# PecanFemto3.net
KiCad netlist of a schematic drawn in EAGLE
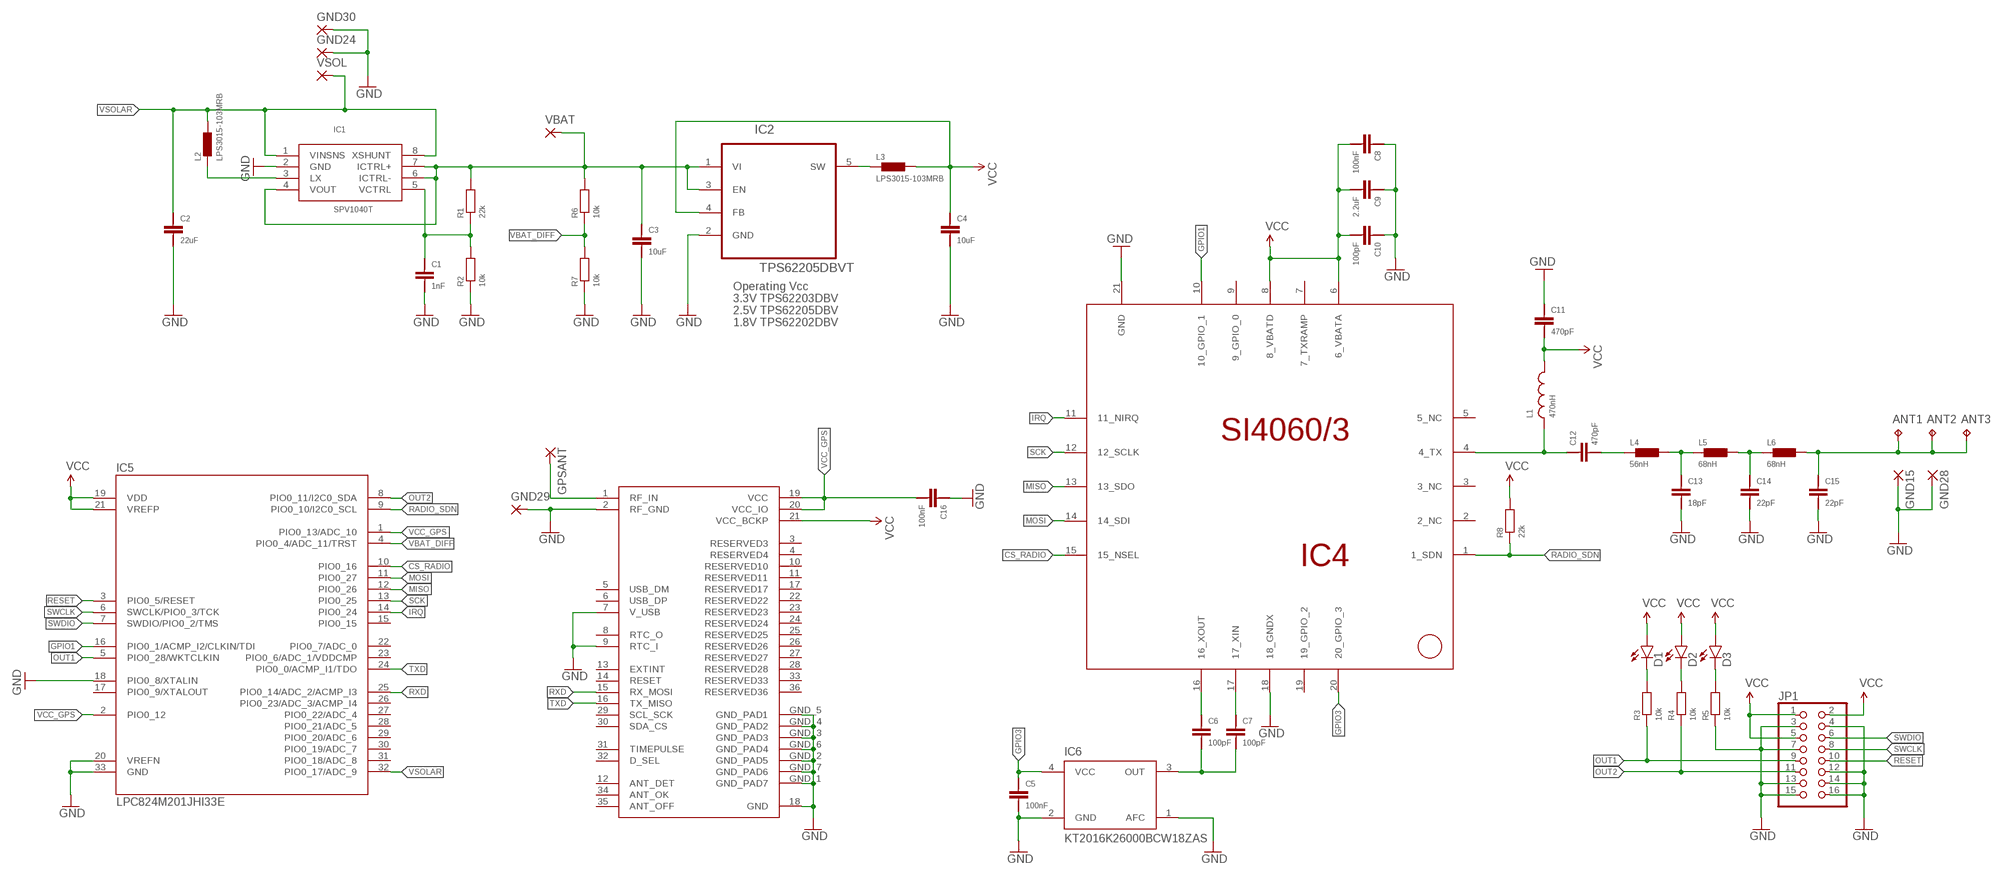
[diagram p0: schematic, sheet 1]

(export (version "E")
  (design (tool "Eeschema 10.0.6"))
  (components
    (comp (ref "ANT1")
      (value "TP")
      (footprint "eagle-import:P1-7")
      (fields (field (name "MPN") "ERJ-3EKF62R0V"))
      (libsource (lib "eagle-import") (part "TP"))
    )
    (comp (ref "ANT2")
      (value "TP")
      (footprint "eagle-import:P1-7")
      (fields (field (name "MPN") "ERJ-3EKF62R0V"))
      (libsource (lib "eagle-import") (part "TP"))
    )
    (comp (ref "ANT3")
      (value "TP")
      (footprint "eagle-import:P1-7")
      (fields (field (name "MPN") "ERJ-3EKF62R0V"))
      (libsource (lib "eagle-import") (part "TP"))
    )
    (comp (ref "C1")
      (value "1nF")
      (footprint "eagle-import:0402")
      (libsource (lib "eagle-import") (part "CAP-0402"))
    )
    (comp (ref "C2")
      (value "22uF")
      (footprint "eagle-import:0805")
      (libsource (lib "eagle-import") (part "CAP-0805"))
    )
    (comp (ref "C3")
      (value "10uF")
      (footprint "eagle-import:0805")
      (libsource (lib "eagle-import") (part "CAP-0805"))
    )
    (comp (ref "C4")
      (value "10uF")
      (footprint "eagle-import:0805")
      (libsource (lib "eagle-import") (part "CAP-0805"))
    )
    (comp (ref "C5")
      (value "100nF")
      (footprint "eagle-import:0402")
      (libsource (lib "eagle-import") (part "CAP-0402"))
    )
    (comp (ref "C6")
      (value "100pF")
      (footprint "eagle-import:0402")
      (libsource (lib "eagle-import") (part "CAP-0402"))
    )
    (comp (ref "C7")
      (value "100pF")
      (footprint "eagle-import:0402")
      (libsource (lib "eagle-import") (part "CAP-0402"))
    )
    (comp (ref "C8")
      (value "100nF")
      (footprint "eagle-import:0402")
      (libsource (lib "eagle-import") (part "CAP-0402"))
    )
    (comp (ref "C9")
      (value "2.2uF")
      (footprint "eagle-import:0402")
      (libsource (lib "eagle-import") (part "CAP-0402"))
    )
    (comp (ref "C10")
      (value "100pF")
      (footprint "eagle-import:0402")
      (libsource (lib "eagle-import") (part "CAP-0402"))
    )
    (comp (ref "C11")
      (value "470pF")
      (footprint "eagle-import:0402")
      (libsource (lib "eagle-import") (part "CAP-0402"))
    )
    (comp (ref "C12")
      (value "470pF")
      (footprint "eagle-import:0402")
      (libsource (lib "eagle-import") (part "CAP-0402"))
    )
    (comp (ref "C13")
      (value "18pF")
      (footprint "eagle-import:0402")
      (libsource (lib "eagle-import") (part "CAP-0402"))
    )
    (comp (ref "C14")
      (value "22pF")
      (footprint "eagle-import:0402")
      (libsource (lib "eagle-import") (part "CAP-0402"))
    )
    (comp (ref "C15")
      (value "22pF")
      (footprint "eagle-import:0402")
      (libsource (lib "eagle-import") (part "CAP-0402"))
    )
    (comp (ref "C16")
      (value "100nF")
      (footprint "eagle-import:0402")
      (libsource (lib "eagle-import") (part "CAP-0402"))
    )
    (comp (ref "D1")
      (value "LED0603")
      (footprint "eagle-import:LED-0603")
      (libsource (lib "eagle-import") (part "LED0603"))
    )
    (comp (ref "D2")
      (value "LED0603")
      (footprint "eagle-import:LED-0603")
      (libsource (lib "eagle-import") (part "LED0603"))
    )
    (comp (ref "D3")
      (value "LED0603")
      (footprint "eagle-import:LED-0603")
      (libsource (lib "eagle-import") (part "LED0603"))
    )
    (comp (ref "GND15")
      (value "SMD2")
      (footprint "eagle-import:SMD1,27-2,54")
      (libsource (lib "eagle-import") (part "SMD2"))
    )
    (comp (ref "GND24")
      (value "SMD2")
      (footprint "eagle-import:SMD1,27-2,54")
      (libsource (lib "eagle-import") (part "SMD2"))
    )
    (comp (ref "GND28")
      (value "SMD2")
      (footprint "eagle-import:SMD1,27-2,54")
      (libsource (lib "eagle-import") (part "SMD2"))
    )
    (comp (ref "GND29")
      (value "SMD2")
      (footprint "eagle-import:SMD1,27-2,54")
      (libsource (lib "eagle-import") (part "SMD2"))
    )
    (comp (ref "GND30")
      (value "SMD2")
      (footprint "eagle-import:SMD1,27-2,54")
      (libsource (lib "eagle-import") (part "SMD2"))
    )
    (comp (ref "GPSANT")
      (value "SMD2")
      (footprint "eagle-import:SMD1,27-2,54")
      (libsource (lib "eagle-import") (part "SMD2"))
    )
    (comp (ref "IC1")
      (value "SPV1040T")
      (footprint "eagle-import:TSSOP8")
      (libsource (lib "eagle-import") (part "SPV1040"))
    )
    (comp (ref "IC2")
      (value "TPS62205DBVT")
      (footprint "eagle-import:SOT95P280X145-5N")
      (fields (field (name "MPN") "TPS62203DBVT") (field (name "MF") "TEXAS INSTRUMENTS"))
      (libsource (lib "eagle-import") (part "TPS62203DBVT"))
    )
    (comp (ref "IC3")
      (value "EVA7M")
      (footprint "eagle-import:EVA7M")
      (libsource (lib "eagle-import") (part "EVA7M"))
    )
    (comp (ref "IC4")
      (value "SI4060/3")
      (footprint "eagle-import:QFN-20")
      (libsource (lib "eagle-import") (part "SI4060/3"))
    )
    (comp (ref "IC5")
      (value "LPC824M201JHI33E")
      (footprint "eagle-import:QFN65P500X500X100-33N")
      (libsource (lib "eagle-import") (part "LPC824M201JHI33E"))
    )
    (comp (ref "IC6")
      (value "KT2016K26000BCW18ZAS")
      (footprint "eagle-import:TCXO_2.0X1.6")
      (libsource (lib "eagle-import") (part "TXC_7Z"))
    )
    (comp (ref "JP1")
      (value "PINHD-2X8")
      (footprint "eagle-import:2X08")
      (libsource (lib "eagle-import") (part "PINHD-2X8"))
    )
    (comp (ref "L1")
      (value "470nH")
      (footprint "eagle-import:0805")
      (libsource (lib "eagle-import") (part "INDUCTOR0805"))
    )
    (comp (ref "L2")
      (value "LPS3015-103MRB")
      (footprint "eagle-import:LPS3015")
      (libsource (lib "eagle-import") (part "IND-LPS3015"))
    )
    (comp (ref "L3")
      (value "LPS3015-103MRB")
      (footprint "eagle-import:LPS3015")
      (libsource (lib "eagle-import") (part "IND-LPS3015"))
    )
    (comp (ref "L4")
      (value "56nH")
      (footprint "eagle-import:0402")
      (libsource (lib "eagle-import") (part "IND-0402"))
    )
    (comp (ref "L5")
      (value "68nH")
      (footprint "eagle-import:0402")
      (libsource (lib "eagle-import") (part "IND-0402"))
    )
    (comp (ref "L6")
      (value "68nH")
      (footprint "eagle-import:0402")
      (libsource (lib "eagle-import") (part "IND-0402"))
    )
    (comp (ref "R1")
      (value "22k")
      (footprint "eagle-import:0402")
      (libsource (lib "eagle-import") (part "RES-0402"))
    )
    (comp (ref "R2")
      (value "10k")
      (footprint "eagle-import:0402")
      (libsource (lib "eagle-import") (part "RES-0402"))
    )
    (comp (ref "R3")
      (value "10k")
      (footprint "eagle-import:0402")
      (libsource (lib "eagle-import") (part "RES-0402"))
    )
    (comp (ref "R4")
      (value "10k")
      (footprint "eagle-import:0402")
      (libsource (lib "eagle-import") (part "RES-0402"))
    )
    (comp (ref "R5")
      (value "10k")
      (footprint "eagle-import:0402")
      (libsource (lib "eagle-import") (part "RES-0402"))
    )
    (comp (ref "R6")
      (value "10k")
      (footprint "eagle-import:0402")
      (libsource (lib "eagle-import") (part "RES-0402"))
    )
    (comp (ref "R7")
      (value "10k")
      (footprint "eagle-import:0402")
      (libsource (lib "eagle-import") (part "RES-0402"))
    )
    (comp (ref "R8")
      (value "22k")
      (footprint "eagle-import:0402")
      (libsource (lib "eagle-import") (part "RES-0402"))
    )
    (comp (ref "VBAT")
      (value "SMD2")
      (footprint "eagle-import:SMD1,27-2,54")
      (libsource (lib "eagle-import") (part "SMD2"))
    )
    (comp (ref "VSOL")
      (value "SMD2")
      (footprint "eagle-import:SMD1,27-2,54")
      (libsource (lib "eagle-import") (part "SMD2"))
    )
  )
  (nets
    (net (code "1") (name "CS_RADIO") (class "Default")
      (node (ref "IC4") (pin "15") (pinfunction "15_NSEL_15") (pintype "bidirectional"))
      (node (ref "IC5") (pin "10") (pinfunction "PIO0_16_10") (pintype "bidirectional"))
    )
    (net (code "2") (name "GND") (class "Default")
      (node (ref "C1") (pin "P$1") (pinfunction "1_P$1") (pintype "passive"))
      (node (ref "C10") (pin "P$2") (pinfunction "2_P$2") (pintype "passive"))
      (node (ref "C11") (pin "P$2") (pinfunction "2_P$2") (pintype "passive"))
      (node (ref "C13") (pin "P$1") (pinfunction "1_P$1") (pintype "passive"))
      (node (ref "C14") (pin "P$1") (pinfunction "1_P$1") (pintype "passive"))
      (node (ref "C15") (pin "P$1") (pinfunction "1_P$1") (pintype "passive"))
      (node (ref "C16") (pin "P$2") (pinfunction "2_P$2") (pintype "passive"))
      (node (ref "C2") (pin "P$1") (pinfunction "1_P$1") (pintype "passive"))
      (node (ref "C3") (pin "P$1") (pinfunction "1_P$1") (pintype "passive"))
      (node (ref "C4") (pin "P$1") (pinfunction "1_P$1") (pintype "passive"))
      (node (ref "C5") (pin "P$1") (pinfunction "1_P$1") (pintype "passive"))
      (node (ref "C8") (pin "P$2") (pinfunction "2_P$2") (pintype "passive"))
      (node (ref "C9") (pin "P$2") (pinfunction "2_P$2") (pintype "passive"))
      (node (ref "GND15") (pin "1") (pinfunction "P_1") (pintype "passive"))
      (node (ref "GND24") (pin "1") (pinfunction "P_1") (pintype "passive"))
      (node (ref "GND28") (pin "1") (pinfunction "P_1") (pintype "passive"))
      (node (ref "GND29") (pin "1") (pinfunction "P_1") (pintype "passive"))
      (node (ref "GND30") (pin "1") (pinfunction "P_1") (pintype "passive"))
      (node (ref "IC1") (pin "2") (pinfunction "GND_2") (pintype "bidirectional"))
      (node (ref "IC2") (pin "2") (pinfunction "GND_2") (pintype "passive"))
      (node (ref "IC3") (pin "18") (pinfunction "GND_18") (pintype "bidirectional"))
      (node (ref "IC3") (pin "2") (pinfunction "RF_GND_2") (pintype "bidirectional"))
      (node (ref "IC3") (pin "7") (pinfunction "V_USB_7") (pintype "bidirectional"))
      (node (ref "IC3") (pin "9") (pinfunction "RTC_I_9") (pintype "bidirectional"))
      (node (ref "IC3") (pin "GND_1") (pinfunction "GND_PAD7_GND_1") (pintype "bidirectional"))
      (node (ref "IC3") (pin "GND_2") (pinfunction "GND_PAD5_GND_2") (pintype "bidirectional"))
      (node (ref "IC3") (pin "GND_3") (pinfunction "GND_PAD3_GND_3") (pintype "bidirectional"))
      (node (ref "IC3") (pin "GND_4") (pinfunction "GND_PAD2_GND_4") (pintype "bidirectional"))
      (node (ref "IC3") (pin "GND_5") (pinfunction "GND_PAD1_GND_5") (pintype "bidirectional"))
      (node (ref "IC3") (pin "GND_6") (pinfunction "GND_PAD4_GND_6") (pintype "bidirectional"))
      (node (ref "IC3") (pin "GND_7") (pinfunction "GND_PAD6_GND_7") (pintype "bidirectional"))
      (node (ref "IC4") (pin "18") (pinfunction "18_GNDX_18") (pintype "bidirectional"))
      (node (ref "IC4") (pin "21") (pinfunction "GND_21") (pintype "bidirectional"))
      (node (ref "IC5") (pin "18") (pinfunction "PIO0_8/XTALIN_18") (pintype "bidirectional"))
      (node (ref "IC5") (pin "20") (pinfunction "VREFN_20") (pintype "bidirectional"))
      (node (ref "IC5") (pin "33") (pinfunction "GND_33") (pintype "bidirectional"))
      (node (ref "IC6") (pin "1") (pinfunction "AFC_1") (pintype "bidirectional"))
      (node (ref "IC6") (pin "2") (pinfunction "GND_2") (pintype "bidirectional"))
      (node (ref "JP1") (pin "12") (pinfunction "12_12") (pintype "passive"))
      (node (ref "JP1") (pin "13") (pinfunction "13_13") (pintype "passive"))
      (node (ref "JP1") (pin "14") (pinfunction "14_14") (pintype "passive"))
      (node (ref "JP1") (pin "15") (pinfunction "15_15") (pintype "passive"))
      (node (ref "JP1") (pin "16") (pinfunction "16_16") (pintype "passive"))
      (node (ref "JP1") (pin "3") (pinfunction "3_3") (pintype "passive"))
      (node (ref "JP1") (pin "4") (pinfunction "4_4") (pintype "passive"))
      (node (ref "JP1") (pin "7") (pinfunction "7_7") (pintype "passive"))
      (node (ref "R2") (pin "P$1") (pinfunction "1_P$1") (pintype "passive"))
      (node (ref "R5") (pin "P$1") (pinfunction "1_P$1") (pintype "passive"))
      (node (ref "R7") (pin "P$1") (pinfunction "1_P$1") (pintype "passive"))
    )
    (net (code "3") (name "GPIO1") (class "Default")
      (node (ref "IC4") (pin "10") (pinfunction "10_GPIO_1_10") (pintype "bidirectional"))
      (node (ref "IC5") (pin "16") (pinfunction "PIO0_1/ACMP_I2/CLKIN/TDI_16") (pintype "bidirectional"))
    )
    (net (code "4") (name "GPIO3") (class "Default")
      (node (ref "C5") (pin "P$2") (pinfunction "2_P$2") (pintype "passive"))
      (node (ref "IC4") (pin "20") (pinfunction "20_GPIO_3_20") (pintype "bidirectional"))
      (node (ref "IC6") (pin "4") (pinfunction "VCC_4") (pintype "bidirectional"))
    )
    (net (code "5") (name "IRQ") (class "Default")
      (node (ref "IC4") (pin "11") (pinfunction "11_NIRQ_11") (pintype "bidirectional"))
      (node (ref "IC5") (pin "14") (pinfunction "PIO0_24_14") (pintype "bidirectional"))
    )
    (net (code "6") (name "MISO") (class "Default")
      (node (ref "IC4") (pin "13") (pinfunction "13_SDO_13") (pintype "bidirectional"))
      (node (ref "IC5") (pin "12") (pinfunction "PIO0_26_12") (pintype "bidirectional"))
    )
    (net (code "7") (name "MOSI") (class "Default")
      (node (ref "IC4") (pin "14") (pinfunction "14_SDI_14") (pintype "bidirectional"))
      (node (ref "IC5") (pin "11") (pinfunction "PIO0_27_11") (pintype "bidirectional"))
    )
    (net (code "8") (name "Net-(C1-2)") (class "Default")
      (node (ref "C1") (pin "P$2") (pinfunction "2_P$2") (pintype "passive"))
      (node (ref "IC1") (pin "5") (pinfunction "VCTRL_5") (pintype "bidirectional"))
      (node (ref "R1") (pin "P$1") (pinfunction "1_P$1") (pintype "passive"))
      (node (ref "R2") (pin "P$2") (pinfunction "2_P$2") (pintype "passive"))
    )
    (net (code "9") (name "Net-(C3-2)") (class "Default")
      (node (ref "C3") (pin "P$2") (pinfunction "2_P$2") (pintype "passive"))
      (node (ref "IC1") (pin "4") (pinfunction "VOUT_4") (pintype "bidirectional"))
      (node (ref "IC1") (pin "6") (pinfunction "ICTRL-_6") (pintype "bidirectional"))
      (node (ref "IC1") (pin "7") (pinfunction "ICTRL+_7") (pintype "bidirectional"))
      (node (ref "IC2") (pin "1") (pinfunction "VI_1") (pintype "power_in"))
      (node (ref "IC2") (pin "3") (pinfunction "EN_3") (pintype "input"))
      (node (ref "R1") (pin "P$2") (pinfunction "2_P$2") (pintype "passive"))
      (node (ref "R6") (pin "P$2") (pinfunction "2_P$2") (pintype "passive"))
      (node (ref "VBAT") (pin "1") (pinfunction "P_1") (pintype "passive"))
    )
    (net (code "10") (name "Net-(C6-1)") (class "Default")
      (node (ref "C6") (pin "P$1") (pinfunction "1_P$1") (pintype "passive"))
      (node (ref "C7") (pin "P$1") (pinfunction "1_P$1") (pintype "passive"))
      (node (ref "IC6") (pin "3") (pinfunction "OUT_3") (pintype "bidirectional"))
    )
    (net (code "11") (name "Net-(C6-2)") (class "Default")
      (node (ref "C6") (pin "P$2") (pinfunction "2_P$2") (pintype "passive"))
      (node (ref "IC4") (pin "16") (pinfunction "16_XOUT_16") (pintype "bidirectional"))
    )
    (net (code "12") (name "Net-(C7-2)") (class "Default")
      (node (ref "C7") (pin "P$2") (pinfunction "2_P$2") (pintype "passive"))
      (node (ref "IC4") (pin "17") (pinfunction "17_XIN_17") (pintype "bidirectional"))
    )
    (net (code "13") (name "Net-(C12-1)") (class "Default")
      (node (ref "C12") (pin "P$1") (pinfunction "1_P$1") (pintype "passive"))
      (node (ref "L4") (pin "P$1") (pinfunction "1_P$1") (pintype "passive"))
    )
    (net (code "14") (name "Net-(C12-2)") (class "Default")
      (node (ref "C12") (pin "P$2") (pinfunction "2_P$2") (pintype "passive"))
      (node (ref "IC4") (pin "4") (pinfunction "4_TX_4") (pintype "bidirectional"))
      (node (ref "L1") (pin "1") (pinfunction "1_1") (pintype "passive"))
    )
    (net (code "15") (name "Net-(C13-2)") (class "Default")
      (node (ref "C13") (pin "P$2") (pinfunction "2_P$2") (pintype "passive"))
      (node (ref "L4") (pin "P$2") (pinfunction "2_P$2") (pintype "passive"))
      (node (ref "L5") (pin "P$1") (pinfunction "1_P$1") (pintype "passive"))
    )
    (net (code "16") (name "Net-(C14-2)") (class "Default")
      (node (ref "C14") (pin "P$2") (pinfunction "2_P$2") (pintype "passive"))
      (node (ref "L5") (pin "P$2") (pinfunction "2_P$2") (pintype "passive"))
      (node (ref "L6") (pin "P$1") (pinfunction "1_P$1") (pintype "passive"))
    )
    (net (code "17") (name "Net-(C15-2)") (class "Default")
      (node (ref "ANT1") (pin "TP") (pinfunction "TP_TP") (pintype "input"))
      (node (ref "ANT2") (pin "TP") (pinfunction "TP_TP") (pintype "input"))
      (node (ref "ANT3") (pin "TP") (pinfunction "TP_TP") (pintype "input"))
      (node (ref "C15") (pin "P$2") (pinfunction "2_P$2") (pintype "passive"))
      (node (ref "L6") (pin "P$2") (pinfunction "2_P$2") (pintype "passive"))
    )
    (net (code "18") (name "Net-(GPSANT-P)") (class "Default")
      (node (ref "GPSANT") (pin "1") (pinfunction "P_1") (pintype "passive"))
      (node (ref "IC3") (pin "1") (pinfunction "RF_IN_1") (pintype "bidirectional"))
    )
    (net (code "19") (name "Net-(IC1-LX)") (class "Default")
      (node (ref "IC1") (pin "3") (pinfunction "LX_3") (pintype "bidirectional"))
      (node (ref "L2") (pin "1_1") (pinfunction "1_1_1") (pintype "passive"))
      (node (ref "L2") (pin "1_2") (pinfunction "1_1_2") (pintype "passive"))
      (node (ref "L2") (pin "1_3") (pinfunction "1_1_3") (pintype "passive"))
      (node (ref "L2") (pin "1_4") (pinfunction "1_1_4") (pintype "passive"))
      (node (ref "L2") (pin "1_5") (pinfunction "1_1_5") (pintype "passive"))
      (node (ref "L2") (pin "1_6") (pinfunction "1_1_6") (pintype "passive"))
      (node (ref "L2") (pin "1_7") (pinfunction "1_1_7") (pintype "passive"))
      (node (ref "L2") (pin "1_8") (pinfunction "1_1_8") (pintype "passive"))
      (node (ref "L2") (pin "1_9") (pinfunction "1_1_9") (pintype "passive"))
    )
    (net (code "20") (name "Net-(IC2-SW)") (class "Default")
      (node (ref "IC2") (pin "5") (pinfunction "SW_5") (pintype "output"))
      (node (ref "L3") (pin "1_1") (pinfunction "1_1_1") (pintype "passive"))
      (node (ref "L3") (pin "1_2") (pinfunction "1_1_2") (pintype "passive"))
      (node (ref "L3") (pin "1_3") (pinfunction "1_1_3") (pintype "passive"))
      (node (ref "L3") (pin "1_4") (pinfunction "1_1_4") (pintype "passive"))
      (node (ref "L3") (pin "1_5") (pinfunction "1_1_5") (pintype "passive"))
      (node (ref "L3") (pin "1_6") (pinfunction "1_1_6") (pintype "passive"))
      (node (ref "L3") (pin "1_7") (pinfunction "1_1_7") (pintype "passive"))
      (node (ref "L3") (pin "1_8") (pinfunction "1_1_8") (pintype "passive"))
      (node (ref "L3") (pin "1_9") (pinfunction "1_1_9") (pintype "passive"))
    )
    (net (code "21") (name "Net-(R3-2)") (class "Default")
      (node (ref "D1") (pin "C") (pinfunction "C_C") (pintype "passive"))
      (node (ref "R3") (pin "P$2") (pinfunction "2_P$2") (pintype "passive"))
    )
    (net (code "22") (name "Net-(R4-2)") (class "Default")
      (node (ref "D2") (pin "C") (pinfunction "C_C") (pintype "passive"))
      (node (ref "R4") (pin "P$2") (pinfunction "2_P$2") (pintype "passive"))
    )
    (net (code "23") (name "Net-(R5-2)") (class "Default")
      (node (ref "D3") (pin "C") (pinfunction "C_C") (pintype "passive"))
      (node (ref "R5") (pin "P$2") (pinfunction "2_P$2") (pintype "passive"))
    )
    (net (code "24") (name "OUT1") (class "Default")
      (node (ref "IC5") (pin "5") (pinfunction "PIO0_28/WKTCLKIN_5") (pintype "bidirectional"))
      (node (ref "JP1") (pin "9") (pinfunction "9_9") (pintype "passive"))
      (node (ref "R3") (pin "P$1") (pinfunction "1_P$1") (pintype "passive"))
    )
    (net (code "25") (name "OUT2") (class "Default")
      (node (ref "IC5") (pin "8") (pinfunction "PIO0_11/I2C0_SDA_8") (pintype "bidirectional"))
      (node (ref "JP1") (pin "11") (pinfunction "11_11") (pintype "passive"))
      (node (ref "R4") (pin "P$1") (pinfunction "1_P$1") (pintype "passive"))
    )
    (net (code "26") (name "RADIO_SDN") (class "Default")
      (node (ref "IC4") (pin "1") (pinfunction "1_SDN_1") (pintype "bidirectional"))
      (node (ref "IC5") (pin "9") (pinfunction "PIO0_10/I2C0_SCL_9") (pintype "bidirectional"))
      (node (ref "R8") (pin "P$1") (pinfunction "1_P$1") (pintype "passive"))
    )
    (net (code "27") (name "RESET") (class "Default")
      (node (ref "IC5") (pin "3") (pinfunction "PIO0_5/RESET_3") (pintype "bidirectional"))
      (node (ref "JP1") (pin "10") (pinfunction "10_10") (pintype "passive"))
    )
    (net (code "28") (name "RXD") (class "Default")
      (node (ref "IC3") (pin "15") (pinfunction "RX_MOSI_15") (pintype "bidirectional"))
      (node (ref "IC5") (pin "25") (pinfunction "PIO0_14/ADC_2/ACMP_I3_25") (pintype "bidirectional"))
    )
    (net (code "29") (name "SCK") (class "Default")
      (node (ref "IC4") (pin "12") (pinfunction "12_SCLK_12") (pintype "bidirectional"))
      (node (ref "IC5") (pin "13") (pinfunction "PIO0_25_13") (pintype "bidirectional"))
    )
    (net (code "30") (name "SWCLK") (class "Default")
      (node (ref "IC5") (pin "6") (pinfunction "SWCLK/PIO0_3/TCK_6") (pintype "bidirectional"))
      (node (ref "JP1") (pin "8") (pinfunction "8_8") (pintype "passive"))
    )
    (net (code "31") (name "SWDIO") (class "Default")
      (node (ref "IC5") (pin "7") (pinfunction "SWDIO/PIO0_2/TMS_7") (pintype "bidirectional"))
      (node (ref "JP1") (pin "6") (pinfunction "6_6") (pintype "passive"))
    )
    (net (code "32") (name "TXD") (class "Default")
      (node (ref "IC3") (pin "16") (pinfunction "TX_MISO_16") (pintype "bidirectional"))
      (node (ref "IC5") (pin "24") (pinfunction "PIO0_0/ACMP_I1/TDO_24") (pintype "bidirectional"))
    )
    (net (code "33") (name "VBAT_DIFF") (class "Default")
      (node (ref "IC5") (pin "4") (pinfunction "PIO0_4/ADC_11/TRST_4") (pintype "bidirectional"))
      (node (ref "R6") (pin "P$1") (pinfunction "1_P$1") (pintype "passive"))
      (node (ref "R7") (pin "P$2") (pinfunction "2_P$2") (pintype "passive"))
    )
    (net (code "34") (name "VCC") (class "Default")
      (node (ref "C10") (pin "P$1") (pinfunction "1_P$1") (pintype "passive"))
      (node (ref "C11") (pin "P$1") (pinfunction "1_P$1") (pintype "passive"))
      (node (ref "C4") (pin "P$2") (pinfunction "2_P$2") (pintype "passive"))
      (node (ref "C8") (pin "P$1") (pinfunction "1_P$1") (pintype "passive"))
      (node (ref "C9") (pin "P$1") (pinfunction "1_P$1") (pintype "passive"))
      (node (ref "D1") (pin "A") (pinfunction "A_A") (pintype "passive"))
      (node (ref "D2") (pin "A") (pinfunction "A_A") (pintype "passive"))
      (node (ref "D3") (pin "A") (pinfunction "A_A") (pintype "passive"))
      (node (ref "IC2") (pin "4") (pinfunction "FB_4") (pintype "input"))
      (node (ref "IC3") (pin "21") (pinfunction "VCC_BCKP_21") (pintype "bidirectional"))
      (node (ref "IC4") (pin "6") (pinfunction "6_VBATA_6") (pintype "bidirectional"))
      (node (ref "IC4") (pin "8") (pinfunction "8_VBATD_8") (pintype "bidirectional"))
      (node (ref "IC5") (pin "19") (pinfunction "VDD_19") (pintype "bidirectional"))
      (node (ref "IC5") (pin "21") (pinfunction "VREFP_21") (pintype "bidirectional"))
      (node (ref "JP1") (pin "1") (pinfunction "1_1") (pintype "passive"))
      (node (ref "JP1") (pin "2") (pinfunction "2_2") (pintype "passive"))
      (node (ref "JP1") (pin "5") (pinfunction "5_5") (pintype "passive"))
      (node (ref "L1") (pin "2") (pinfunction "2_2") (pintype "passive"))
      (node (ref "L3") (pin "2_1") (pinfunction "2_2_1") (pintype "passive"))
      (node (ref "L3") (pin "2_2") (pinfunction "2_2_2") (pintype "passive"))
      (node (ref "L3") (pin "2_3") (pinfunction "2_2_3") (pintype "passive"))
      (node (ref "L3") (pin "2_4") (pinfunction "2_2_4") (pintype "passive"))
      (node (ref "L3") (pin "2_5") (pinfunction "2_2_5") (pintype "passive"))
      (node (ref "L3") (pin "2_6") (pinfunction "2_2_6") (pintype "passive"))
      (node (ref "L3") (pin "2_7") (pinfunction "2_2_7") (pintype "passive"))
      (node (ref "L3") (pin "2_8") (pinfunction "2_2_8") (pintype "passive"))
      (node (ref "L3") (pin "2_9") (pinfunction "2_2_9") (pintype "passive"))
      (node (ref "R8") (pin "P$2") (pinfunction "2_P$2") (pintype "passive"))
    )
    (net (code "35") (name "VCC_GPS") (class "Default")
      (node (ref "C16") (pin "P$1") (pinfunction "1_P$1") (pintype "passive"))
      (node (ref "IC3") (pin "19") (pinfunction "VCC_19") (pintype "bidirectional"))
      (node (ref "IC3") (pin "20") (pinfunction "VCC_IO_20") (pintype "bidirectional"))
      (node (ref "IC5") (pin "1") (pinfunction "PIO0_13/ADC_10_1") (pintype "bidirectional"))
      (node (ref "IC5") (pin "2") (pinfunction "PIO0_12_2") (pintype "bidirectional"))
    )
    (net (code "36") (name "VSOLAR") (class "Default")
      (node (ref "C2") (pin "P$2") (pinfunction "2_P$2") (pintype "passive"))
      (node (ref "IC1") (pin "1") (pinfunction "VINSNS_1") (pintype "bidirectional"))
      (node (ref "IC1") (pin "8") (pinfunction "XSHUNT_8") (pintype "bidirectional"))
      (node (ref "IC5") (pin "32") (pinfunction "PIO0_17/ADC_9_32") (pintype "bidirectional"))
      (node (ref "L2") (pin "2_1") (pinfunction "2_2_1") (pintype "passive"))
      (node (ref "L2") (pin "2_2") (pinfunction "2_2_2") (pintype "passive"))
      (node (ref "L2") (pin "2_3") (pinfunction "2_2_3") (pintype "passive"))
      (node (ref "L2") (pin "2_4") (pinfunction "2_2_4") (pintype "passive"))
      (node (ref "L2") (pin "2_5") (pinfunction "2_2_5") (pintype "passive"))
      (node (ref "L2") (pin "2_6") (pinfunction "2_2_6") (pintype "passive"))
      (node (ref "L2") (pin "2_7") (pinfunction "2_2_7") (pintype "passive"))
      (node (ref "L2") (pin "2_8") (pinfunction "2_2_8") (pintype "passive"))
      (node (ref "L2") (pin "2_9") (pinfunction "2_2_9") (pintype "passive"))
      (node (ref "VSOL") (pin "1") (pinfunction "P_1") (pintype "passive"))
    )
    (net (code "37") (name "unconnected-(IC3-ANT_DET-Pad12)") (class "Default")
      (node (ref "IC3") (pin "12") (pinfunction "ANT_DET_12") (pintype "bidirectional"))
    )
    (net (code "38") (name "unconnected-(IC3-ANT_OFF-Pad35)") (class "Default")
      (node (ref "IC3") (pin "35") (pinfunction "ANT_OFF_35") (pintype "bidirectional"))
    )
    (net (code "39") (name "unconnected-(IC3-ANT_OK-Pad34)") (class "Default")
      (node (ref "IC3") (pin "34") (pinfunction "ANT_OK_34") (pintype "bidirectional"))
    )
    (net (code "40") (name "unconnected-(IC3-D_SEL-Pad32)") (class "Default")
      (node (ref "IC3") (pin "32") (pinfunction "D_SEL_32") (pintype "bidirectional"))
    )
    (net (code "41") (name "unconnected-(IC3-EXTINT-Pad13)") (class "Default")
      (node (ref "IC3") (pin "13") (pinfunction "EXTINT_13") (pintype "bidirectional"))
    )
    (net (code "42") (name "unconnected-(IC3-RESERVED3-Pad3)") (class "Default")
      (node (ref "IC3") (pin "3") (pinfunction "RESERVED3_3") (pintype "bidirectional"))
    )
    (net (code "43") (name "unconnected-(IC3-RESERVED4-Pad4)") (class "Default")
      (node (ref "IC3") (pin "4") (pinfunction "RESERVED4_4") (pintype "bidirectional"))
    )
    (net (code "44") (name "unconnected-(IC3-RESERVED10-Pad10)") (class "Default")
      (node (ref "IC3") (pin "10") (pinfunction "RESERVED10_10") (pintype "bidirectional"))
    )
    (net (code "45") (name "unconnected-(IC3-RESERVED11-Pad11)") (class "Default")
      (node (ref "IC3") (pin "11") (pinfunction "RESERVED11_11") (pintype "bidirectional"))
    )
    (net (code "46") (name "unconnected-(IC3-RESERVED17-Pad17)") (class "Default")
      (node (ref "IC3") (pin "17") (pinfunction "RESERVED17_17") (pintype "bidirectional"))
    )
    (net (code "47") (name "unconnected-(IC3-RESERVED22-Pad22)") (class "Default")
      (node (ref "IC3") (pin "22") (pinfunction "RESERVED22_22") (pintype "bidirectional"))
    )
    (net (code "48") (name "unconnected-(IC3-RESERVED23-Pad23)") (class "Default")
      (node (ref "IC3") (pin "23") (pinfunction "RESERVED23_23") (pintype "bidirectional"))
    )
    (net (code "49") (name "unconnected-(IC3-RESERVED24-Pad24)") (class "Default")
      (node (ref "IC3") (pin "24") (pinfunction "RESERVED24_24") (pintype "bidirectional"))
    )
    (net (code "50") (name "unconnected-(IC3-RESERVED25-Pad25)") (class "Default")
      (node (ref "IC3") (pin "25") (pinfunction "RESERVED25_25") (pintype "bidirectional"))
    )
    (net (code "51") (name "unconnected-(IC3-RESERVED26-Pad26)") (class "Default")
      (node (ref "IC3") (pin "26") (pinfunction "RESERVED26_26") (pintype "bidirectional"))
    )
    (net (code "52") (name "unconnected-(IC3-RESERVED27-Pad27)") (class "Default")
      (node (ref "IC3") (pin "27") (pinfunction "RESERVED27_27") (pintype "bidirectional"))
    )
    (net (code "53") (name "unconnected-(IC3-RESERVED28-Pad28)") (class "Default")
      (node (ref "IC3") (pin "28") (pinfunction "RESERVED28_28") (pintype "bidirectional"))
    )
    (net (code "54") (name "unconnected-(IC3-RESERVED33-Pad33)") (class "Default")
      (node (ref "IC3") (pin "33") (pinfunction "RESERVED33_33") (pintype "bidirectional"))
    )
    (net (code "55") (name "unconnected-(IC3-RESERVED36-Pad36)") (class "Default")
      (node (ref "IC3") (pin "36") (pinfunction "RESERVED36_36") (pintype "bidirectional"))
    )
    (net (code "56") (name "unconnected-(IC3-RESET-Pad14)") (class "Default")
      (node (ref "IC3") (pin "14") (pinfunction "RESET_14") (pintype "bidirectional"))
    )
    (net (code "57") (name "unconnected-(IC3-RTC_O-Pad8)") (class "Default")
      (node (ref "IC3") (pin "8") (pinfunction "RTC_O_8") (pintype "bidirectional"))
    )
    (net (code "58") (name "unconnected-(IC3-SCL_SCK-Pad29)") (class "Default")
      (node (ref "IC3") (pin "29") (pinfunction "SCL_SCK_29") (pintype "bidirectional"))
    )
    (net (code "59") (name "unconnected-(IC3-SDA_CS-Pad30)") (class "Default")
      (node (ref "IC3") (pin "30") (pinfunction "SDA_CS_30") (pintype "bidirectional"))
    )
    (net (code "60") (name "unconnected-(IC3-TIMEPULSE-Pad31)") (class "Default")
      (node (ref "IC3") (pin "31") (pinfunction "TIMEPULSE_31") (pintype "bidirectional"))
    )
    (net (code "61") (name "unconnected-(IC3-USB_DM-Pad5)") (class "Default")
      (node (ref "IC3") (pin "5") (pinfunction "USB_DM_5") (pintype "bidirectional"))
    )
    (net (code "62") (name "unconnected-(IC3-USB_DP-Pad6)") (class "Default")
      (node (ref "IC3") (pin "6") (pinfunction "USB_DP_6") (pintype "bidirectional"))
    )
    (net (code "63") (name "unconnected-(IC4-2_NC-Pad2)") (class "Default")
      (node (ref "IC4") (pin "2") (pinfunction "2_NC_2") (pintype "bidirectional"))
    )
    (net (code "64") (name "unconnected-(IC4-3_NC-Pad3)") (class "Default")
      (node (ref "IC4") (pin "3") (pinfunction "3_NC_3") (pintype "bidirectional"))
    )
    (net (code "65") (name "unconnected-(IC4-5_NC-Pad5)") (class "Default")
      (node (ref "IC4") (pin "5") (pinfunction "5_NC_5") (pintype "bidirectional"))
    )
    (net (code "66") (name "unconnected-(IC4-7_TXRAMP-Pad7)") (class "Default")
      (node (ref "IC4") (pin "7") (pinfunction "7_TXRAMP_7") (pintype "bidirectional"))
    )
    (net (code "67") (name "unconnected-(IC4-9_GPIO_0-Pad9)") (class "Default")
      (node (ref "IC4") (pin "9") (pinfunction "9_GPIO_0_9") (pintype "bidirectional"))
    )
    (net (code "68") (name "unconnected-(IC4-19_GPIO_2-Pad19)") (class "Default")
      (node (ref "IC4") (pin "19") (pinfunction "19_GPIO_2_19") (pintype "bidirectional"))
    )
    (net (code "69") (name "unconnected-(IC5-PIO0_6{slash}ADC_1{slash}VDDCMP-Pad23)") (class "Default")
      (node (ref "IC5") (pin "23") (pinfunction "PIO0_6/ADC_1/VDDCMP_23") (pintype "bidirectional"))
    )
    (net (code "70") (name "unconnected-(IC5-PIO0_7{slash}ADC_0-Pad22)") (class "Default")
      (node (ref "IC5") (pin "22") (pinfunction "PIO0_7/ADC_0_22") (pintype "bidirectional"))
    )
    (net (code "71") (name "unconnected-(IC5-PIO0_9{slash}XTALOUT-Pad17)") (class "Default")
      (node (ref "IC5") (pin "17") (pinfunction "PIO0_9/XTALOUT_17") (pintype "bidirectional"))
    )
    (net (code "72") (name "unconnected-(IC5-PIO0_15-Pad15)") (class "Default")
      (node (ref "IC5") (pin "15") (pinfunction "PIO0_15_15") (pintype "bidirectional"))
    )
    (net (code "73") (name "unconnected-(IC5-PIO0_18{slash}ADC_8-Pad31)") (class "Default")
      (node (ref "IC5") (pin "31") (pinfunction "PIO0_18/ADC_8_31") (pintype "bidirectional"))
    )
    (net (code "74") (name "unconnected-(IC5-PIO0_19{slash}ADC_7-Pad30)") (class "Default")
      (node (ref "IC5") (pin "30") (pinfunction "PIO0_19/ADC_7_30") (pintype "bidirectional"))
    )
    (net (code "75") (name "unconnected-(IC5-PIO0_20{slash}ADC_6-Pad29)") (class "Default")
      (node (ref "IC5") (pin "29") (pinfunction "PIO0_20/ADC_6_29") (pintype "bidirectional"))
    )
    (net (code "76") (name "unconnected-(IC5-PIO0_21{slash}ADC_5-Pad28)") (class "Default")
      (node (ref "IC5") (pin "28") (pinfunction "PIO0_21/ADC_5_28") (pintype "bidirectional"))
    )
    (net (code "77") (name "unconnected-(IC5-PIO0_22{slash}ADC_4-Pad27)") (class "Default")
      (node (ref "IC5") (pin "27") (pinfunction "PIO0_22/ADC_4_27") (pintype "bidirectional"))
    )
    (net (code "78") (name "unconnected-(IC5-PIO0_23{slash}ADC_3{slash}ACMP_I4-Pad26)") (class "Default")
      (node (ref "IC5") (pin "26") (pinfunction "PIO0_23/ADC_3/ACMP_I4_26") (pintype "bidirectional"))
    )
  )
)
